# BLE_Board_WB55.net
KiCad netlist of a schematic drawn in EAGLE
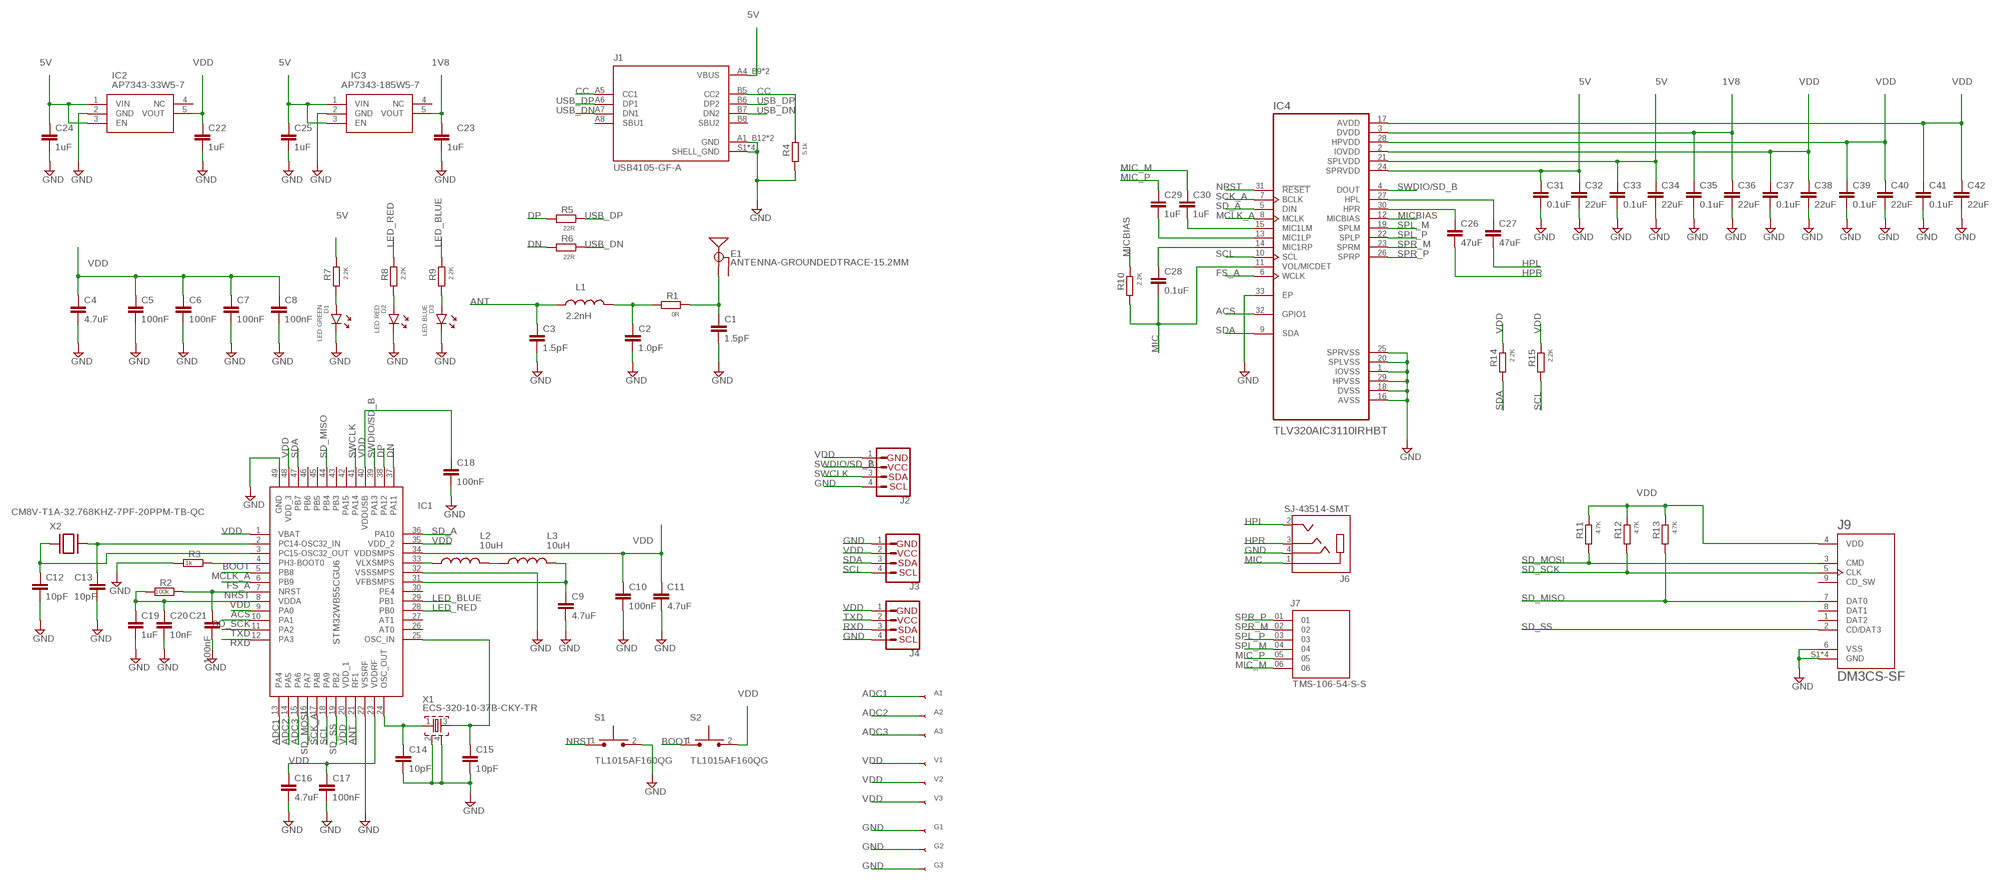
[diagram p0: schematic, sheet 1]

(export (version "E")
  (design (tool "Eeschema 10.0.6"))
  (components
    (comp (ref "A1")
      (value "ATP-50")
      (footprint "eagle-import:ATP-50")
      (libsource (lib "eagle-import") (part "ATP-50"))
    )
    (comp (ref "A2")
      (value "ATP-50")
      (footprint "eagle-import:ATP-50")
      (libsource (lib "eagle-import") (part "ATP-50"))
    )
    (comp (ref "A3")
      (value "ATP-50")
      (footprint "eagle-import:ATP-50")
      (libsource (lib "eagle-import") (part "ATP-50"))
    )
    (comp (ref "C1")
      (value "1.5pF")
      (footprint "eagle-import:RESC0402_N")
      (libsource (lib "eagle-import") (part "CAPACITOR_0402_N"))
    )
    (comp (ref "C2")
      (value "1.0pF")
      (footprint "eagle-import:RESC0402_N")
      (libsource (lib "eagle-import") (part "CAPACITOR_0402_N"))
    )
    (comp (ref "C3")
      (value "1.5pF")
      (footprint "eagle-import:RESC0402_N")
      (libsource (lib "eagle-import") (part "CAPACITOR_0402_N"))
    )
    (comp (ref "C4")
      (value "4.7uF")
      (footprint "eagle-import:RESC0603_N")
      (libsource (lib "eagle-import") (part "CAPACITOR_0603_N"))
    )
    (comp (ref "C5")
      (value "100nF")
      (footprint "eagle-import:RESC0603_N")
      (libsource (lib "eagle-import") (part "CAPACITOR_0603_N"))
    )
    (comp (ref "C6")
      (value "100nF")
      (footprint "eagle-import:RESC0603_N")
      (libsource (lib "eagle-import") (part "CAPACITOR_0603_N"))
    )
    (comp (ref "C7")
      (value "100nF")
      (footprint "eagle-import:RESC0603_N")
      (libsource (lib "eagle-import") (part "CAPACITOR_0603_N"))
    )
    (comp (ref "C8")
      (value "100nF")
      (footprint "eagle-import:RESC0603_N")
      (libsource (lib "eagle-import") (part "CAPACITOR_0603_N"))
    )
    (comp (ref "C9")
      (value "4.7uF")
      (footprint "eagle-import:RESC0603_N")
      (libsource (lib "eagle-import") (part "CAPACITOR_0603_N"))
    )
    (comp (ref "C10")
      (value "100nF")
      (footprint "eagle-import:RESC0603_N")
      (libsource (lib "eagle-import") (part "CAPACITOR_0603_N"))
    )
    (comp (ref "C11")
      (value "4.7uF")
      (footprint "eagle-import:RESC0603_N")
      (libsource (lib "eagle-import") (part "CAPACITOR_0603_N"))
    )
    (comp (ref "C12")
      (value "10pF")
      (footprint "eagle-import:RESC0402_N")
      (libsource (lib "eagle-import") (part "CAPACITOR_0402_N"))
    )
    (comp (ref "C13")
      (value "10pF")
      (footprint "eagle-import:RESC0402_N")
      (libsource (lib "eagle-import") (part "CAPACITOR_0402_N"))
    )
    (comp (ref "C14")
      (value "10pF")
      (footprint "eagle-import:RESC0402_N")
      (libsource (lib "eagle-import") (part "CAPACITOR_0402_N"))
    )
    (comp (ref "C15")
      (value "10pF")
      (footprint "eagle-import:RESC0402_N")
      (libsource (lib "eagle-import") (part "CAPACITOR_0402_N"))
    )
    (comp (ref "C16")
      (value "4.7uF")
      (footprint "eagle-import:RESC0603_N")
      (libsource (lib "eagle-import") (part "CAPACITOR_0603_N"))
    )
    (comp (ref "C17")
      (value "100nF")
      (footprint "eagle-import:RESC0603_N")
      (libsource (lib "eagle-import") (part "CAPACITOR_0603_N"))
    )
    (comp (ref "C18")
      (value "100nF")
      (footprint "eagle-import:RESC0603_N")
      (libsource (lib "eagle-import") (part "CAPACITOR_0603_N"))
    )
    (comp (ref "C19")
      (value "1uF")
      (footprint "eagle-import:RESC0603_N")
      (libsource (lib "eagle-import") (part "CAPACITOR_0603_N"))
    )
    (comp (ref "C20")
      (value "10nF")
      (footprint "eagle-import:RESC0603_N")
      (libsource (lib "eagle-import") (part "CAPACITOR_0603_N"))
    )
    (comp (ref "C21")
      (value "100nF")
      (footprint "eagle-import:RESC0603_N")
      (libsource (lib "eagle-import") (part "CAPACITOR_0603_N"))
    )
    (comp (ref "C22")
      (value "1uF")
      (footprint "eagle-import:RESC0603_N")
      (libsource (lib "eagle-import") (part "CAPACITOR_0603_N"))
    )
    (comp (ref "C23")
      (value "1uF")
      (footprint "eagle-import:RESC0603_N")
      (libsource (lib "eagle-import") (part "CAPACITOR_0603_N"))
    )
    (comp (ref "C24")
      (value "1uF")
      (footprint "eagle-import:RESC0603_N")
      (libsource (lib "eagle-import") (part "CAPACITOR_0603_N"))
    )
    (comp (ref "C25")
      (value "1uF")
      (footprint "eagle-import:RESC0603_N")
      (libsource (lib "eagle-import") (part "CAPACITOR_0603_N"))
    )
    (comp (ref "C26")
      (value "47uF")
      (footprint "eagle-import:RESC0603_N")
      (libsource (lib "eagle-import") (part "CAPACITOR_0603_N"))
    )
    (comp (ref "C27")
      (value "47uF")
      (footprint "eagle-import:RESC0603_N")
      (libsource (lib "eagle-import") (part "CAPACITOR_0603_N"))
    )
    (comp (ref "C28")
      (value "0.1uF")
      (footprint "eagle-import:RESC0603_N")
      (libsource (lib "eagle-import") (part "CAPACITOR_0603_N"))
    )
    (comp (ref "C29")
      (value "1uF")
      (footprint "eagle-import:RESC0603_N")
      (libsource (lib "eagle-import") (part "CAPACITOR_0603_N"))
    )
    (comp (ref "C30")
      (value "1uF")
      (footprint "eagle-import:RESC0603_N")
      (libsource (lib "eagle-import") (part "CAPACITOR_0603_N"))
    )
    (comp (ref "C31")
      (value "0.1uF")
      (footprint "eagle-import:RESC0603_N")
      (libsource (lib "eagle-import") (part "CAPACITOR_0603_N"))
    )
    (comp (ref "C32")
      (value "22uF")
      (footprint "eagle-import:RESC0603_N")
      (libsource (lib "eagle-import") (part "CAPACITOR_0603_N"))
    )
    (comp (ref "C33")
      (value "0.1uF")
      (footprint "eagle-import:RESC0603_N")
      (libsource (lib "eagle-import") (part "CAPACITOR_0603_N"))
    )
    (comp (ref "C34")
      (value "22uF")
      (footprint "eagle-import:RESC0603_N")
      (libsource (lib "eagle-import") (part "CAPACITOR_0603_N"))
    )
    (comp (ref "C35")
      (value "0.1uF")
      (footprint "eagle-import:RESC0603_N")
      (libsource (lib "eagle-import") (part "CAPACITOR_0603_N"))
    )
    (comp (ref "C36")
      (value "22uF")
      (footprint "eagle-import:RESC0603_N")
      (libsource (lib "eagle-import") (part "CAPACITOR_0603_N"))
    )
    (comp (ref "C37")
      (value "0.1uF")
      (footprint "eagle-import:RESC0603_N")
      (libsource (lib "eagle-import") (part "CAPACITOR_0603_N"))
    )
    (comp (ref "C38")
      (value "22uF")
      (footprint "eagle-import:RESC0603_N")
      (libsource (lib "eagle-import") (part "CAPACITOR_0603_N"))
    )
    (comp (ref "C39")
      (value "0.1uF")
      (footprint "eagle-import:RESC0603_N")
      (libsource (lib "eagle-import") (part "CAPACITOR_0603_N"))
    )
    (comp (ref "C40")
      (value "22uF")
      (footprint "eagle-import:RESC0603_N")
      (libsource (lib "eagle-import") (part "CAPACITOR_0603_N"))
    )
    (comp (ref "C41")
      (value "0.1uF")
      (footprint "eagle-import:RESC0603_N")
      (libsource (lib "eagle-import") (part "CAPACITOR_0603_N"))
    )
    (comp (ref "C42")
      (value "22uF")
      (footprint "eagle-import:RESC0603_N")
      (libsource (lib "eagle-import") (part "CAPACITOR_0603_N"))
    )
    (comp (ref "D1")
      (value "LED GREEN")
      (footprint "eagle-import:DIOC0603_N")
      (libsource (lib "eagle-import") (part "LED"))
    )
    (comp (ref "D2")
      (value "LED RED")
      (footprint "eagle-import:DIOC0603_N")
      (libsource (lib "eagle-import") (part "LED"))
    )
    (comp (ref "D3")
      (value "LED BLUE")
      (footprint "eagle-import:DIOC0603_N")
      (libsource (lib "eagle-import") (part "LED"))
    )
    (comp (ref "E1")
      (value "ANTENNA-GROUNDEDTRACE-15.2MM")
      (footprint "eagle-import:TRACE_ANTENNA_2.4GHZ_15.2MM")
      (libsource (lib "eagle-import") (part "ANTENNA-GROUNDEDTRACE-15.2MM"))
    )
    (comp (ref "G1")
      (value "ATP-50")
      (footprint "eagle-import:ATP-50")
      (libsource (lib "eagle-import") (part "ATP-50"))
    )
    (comp (ref "G2")
      (value "ATP-50")
      (footprint "eagle-import:ATP-50")
      (libsource (lib "eagle-import") (part "ATP-50"))
    )
    (comp (ref "G3")
      (value "ATP-50")
      (footprint "eagle-import:ATP-50")
      (libsource (lib "eagle-import") (part "ATP-50"))
    )
    (comp (ref "IC1")
      (value "STM32WB55CGU6")
      (footprint "eagle-import:QFN50P700X700X60-49N")
      (fields (field (name "MOUSER_PART_NUMBER") "511-STM32WB55CGU6"))
      (libsource (lib "eagle-import") (part "STM32WB55CGU6"))
    )
    (comp (ref "IC2")
      (value "AP7343-33W5-7")
      (footprint "eagle-import:SOT95P285X140-5N")
      (fields (field (name "MOUSER_PART_NUMBER") "621-AP7343-33W5-7"))
      (libsource (lib "eagle-import") (part "AP7343-33W5-7"))
    )
    (comp (ref "IC3")
      (value "AP7343-185W5-7")
      (footprint "eagle-import:SOT95P285X140-5N")
      (fields (field (name "MOUSER_PART_NUMBER") "621-AP7343-185W5-7"))
      (libsource (lib "eagle-import") (part "AP7343-185W5-7"))
    )
    (comp (ref "IC4")
      (value "TLV320AIC3110IRHBT")
      (footprint "eagle-import:IC_ADS125H01IRHBT")
      (fields (field (name "MF") "Texas Instruments"))
      (libsource (lib "eagle-import") (part "TLV320AIC3110IRHBT"))
    )
    (comp (ref "J1")
      (value "USB4105-GF-A")
      (footprint "eagle-import:GCT_USB4105-GF-A")
      (fields (field (name "MF") "GCT"))
      (libsource (lib "eagle-import") (part "USB4105-GF-A"))
    )
    (comp (ref "J2")
      (value "QWIIC_CONNECTORJS-1MM")
      (footprint "eagle-import:1X04_1MM_RA")
      (libsource (lib "eagle-import") (part "QWIIC_CONNECTORJS-1MM"))
    )
    (comp (ref "J3")
      (value "QWIIC_CONNECTORJS-1MM")
      (footprint "eagle-import:1X04_1MM_RA")
      (libsource (lib "eagle-import") (part "QWIIC_CONNECTORJS-1MM"))
    )
    (comp (ref "J4")
      (value "QWIIC_CONNECTORJS-1MM")
      (footprint "eagle-import:1X04_1MM_RA")
      (libsource (lib "eagle-import") (part "QWIIC_CONNECTORJS-1MM"))
    )
    (comp (ref "J6")
      (value "SJ-43514-SMT")
      (footprint "eagle-import:CUI_SJ-43514-SMT")
      (fields (field (name "MF") "CUI Devices") (field (name "MP") "SJ-43514-SMT-TR"))
      (libsource (lib "eagle-import") (part "SJ-43514-SMT"))
    )
    (comp (ref "J7")
      (value "TMS-106-54-S-S")
      (footprint "eagle-import:SAMTEC_TMS-106-54-S-S")
      (fields (field (name "MF") "Samtec"))
      (libsource (lib "eagle-import") (part "TMS-106-54-S-S"))
    )
    (comp (ref "J9")
      (value "DM3CS-SF")
      (footprint "eagle-import:HRS_DM3CS-SF")
      (fields (field (name "MF") "Hirose"))
      (libsource (lib "eagle-import") (part "DM3CS-SF"))
    )
    (comp (ref "L1")
      (value "2.2nH")
      (footprint "eagle-import:RESC0402_N")
      (libsource (lib "eagle-import") (part "INDUCTOR_0402_N"))
    )
    (comp (ref "L2")
      (value "10uH")
      (footprint "eagle-import:RESC0603_N")
      (libsource (lib "eagle-import") (part "INDUCTOR_0603_N"))
    )
    (comp (ref "L3")
      (value "10uH")
      (footprint "eagle-import:RESC0603_N")
      (libsource (lib "eagle-import") (part "INDUCTOR_0603_N"))
    )
    (comp (ref "R1")
      (value "0R")
      (footprint "eagle-import:RESC0402_N")
      (libsource (lib "eagle-import") (part "RESISTOR_0402_N"))
    )
    (comp (ref "R2")
      (value "100k")
      (footprint "eagle-import:RESC0603_N")
      (libsource (lib "eagle-import") (part "RESISTOR_0603_N"))
    )
    (comp (ref "R3")
      (value "1k")
      (footprint "eagle-import:RESC0603_N")
      (libsource (lib "eagle-import") (part "RESISTOR_0603_N"))
    )
    (comp (ref "R4")
      (value "5.1k")
      (footprint "eagle-import:RESC0603_N")
      (libsource (lib "eagle-import") (part "RESISTOR_0603_N"))
    )
    (comp (ref "R5")
      (value "22R")
      (footprint "eagle-import:RESC0603_N")
      (libsource (lib "eagle-import") (part "RESISTOR_0603_N"))
    )
    (comp (ref "R6")
      (value "22R")
      (footprint "eagle-import:RESC0603_N")
      (libsource (lib "eagle-import") (part "RESISTOR_0603_N"))
    )
    (comp (ref "R7")
      (value "2.2K")
      (footprint "eagle-import:RESC0603_N")
      (libsource (lib "eagle-import") (part "RESISTOR_0603_N"))
    )
    (comp (ref "R8")
      (value "2.2K")
      (footprint "eagle-import:RESC0603_N")
      (libsource (lib "eagle-import") (part "RESISTOR_0603_N"))
    )
    (comp (ref "R9")
      (value "2.2K")
      (footprint "eagle-import:RESC0603_N")
      (libsource (lib "eagle-import") (part "RESISTOR_0603_N"))
    )
    (comp (ref "R10")
      (value "2.2K")
      (footprint "eagle-import:RESC0603_N")
      (libsource (lib "eagle-import") (part "RESISTOR_0603_N"))
    )
    (comp (ref "R11")
      (value "4.7K")
      (footprint "eagle-import:RESC0603_N")
      (libsource (lib "eagle-import") (part "RESISTOR_0603_N"))
    )
    (comp (ref "R12")
      (value "4.7K")
      (footprint "eagle-import:RESC0603_N")
      (libsource (lib "eagle-import") (part "RESISTOR_0603_N"))
    )
    (comp (ref "R13")
      (value "4.7K")
      (footprint "eagle-import:RESC0603_N")
      (libsource (lib "eagle-import") (part "RESISTOR_0603_N"))
    )
    (comp (ref "R14")
      (value "2.2K")
      (footprint "eagle-import:RESC0603_N")
      (libsource (lib "eagle-import") (part "RESISTOR_0603_N"))
    )
    (comp (ref "R15")
      (value "2.2K")
      (footprint "eagle-import:RESC0603_N")
      (libsource (lib "eagle-import") (part "RESISTOR_0603_N"))
    )
    (comp (ref "S1")
      (value "TL1015AF160QG")
      (footprint "eagle-import:SW_TL1015AF160QG")
      (fields (field (name "MF") "E-Switch"))
      (libsource (lib "eagle-import") (part "TL1015AF160QG"))
    )
    (comp (ref "S2")
      (value "TL1015AF160QG")
      (footprint "eagle-import:SW_TL1015AF160QG")
      (fields (field (name "MF") "E-Switch"))
      (libsource (lib "eagle-import") (part "TL1015AF160QG"))
    )
    (comp (ref "V1")
      (value "ATP-50")
      (footprint "eagle-import:ATP-50")
      (libsource (lib "eagle-import") (part "ATP-50"))
    )
    (comp (ref "V2")
      (value "ATP-50")
      (footprint "eagle-import:ATP-50")
      (libsource (lib "eagle-import") (part "ATP-50"))
    )
    (comp (ref "V3")
      (value "ATP-50")
      (footprint "eagle-import:ATP-50")
      (libsource (lib "eagle-import") (part "ATP-50"))
    )
    (comp (ref "X1")
      (value "ECS-320-10-37B-CKY-TR")
      (footprint "eagle-import:BT-XTAL_2016_N")
      (libsource (lib "eagle-import") (part "XTAL_32MHZ"))
    )
    (comp (ref "X2")
      (value "CM8V-T1A-32.768KHZ-7PF-20PPM-TB-QC")
      (footprint "eagle-import:XTAL_CM8V-T1A-32.768KHZ-7PF-20PPM-TB-QC")
      (fields (field (name "MF") "Micro Crystal AG"))
      (libsource (lib "eagle-import") (part "CM8V-T1A-32.768KHZ-7PF-20PPM-TB-QC"))
    )
  )
  (nets
    (net (code "1") (name "/1V8") (class "Default")
      (node (ref "C23") (pin "1") (pinfunction "1_1") (pintype "passive"))
      (node (ref "C35") (pin "1") (pinfunction "1_1") (pintype "passive"))
      (node (ref "C36") (pin "1") (pinfunction "1_1") (pintype "passive"))
      (node (ref "IC3") (pin "5") (pinfunction "VOUT_5") (pintype "bidirectional"))
      (node (ref "IC4") (pin "3") (pinfunction "DVDD_3") (pintype "power_in"))
    )
    (net (code "2") (name "/5V") (class "Default")
      (node (ref "C24") (pin "1") (pinfunction "1_1") (pintype "passive"))
      (node (ref "C25") (pin "1") (pinfunction "1_1") (pintype "passive"))
      (node (ref "C31") (pin "1") (pinfunction "1_1") (pintype "passive"))
      (node (ref "C32") (pin "1") (pinfunction "1_1") (pintype "passive"))
      (node (ref "C33") (pin "1") (pinfunction "1_1") (pintype "passive"))
      (node (ref "C34") (pin "1") (pinfunction "1_1") (pintype "passive"))
      (node (ref "IC2") (pin "1") (pinfunction "VIN_1") (pintype "bidirectional"))
      (node (ref "IC2") (pin "3") (pinfunction "EN_3") (pintype "bidirectional"))
      (node (ref "IC3") (pin "1") (pinfunction "VIN_1") (pintype "bidirectional"))
      (node (ref "IC3") (pin "3") (pinfunction "EN_3") (pintype "bidirectional"))
      (node (ref "IC4") (pin "21") (pinfunction "SPLVDD_21") (pintype "power_in"))
      (node (ref "IC4") (pin "24") (pinfunction "SPRVDD_24") (pintype "power_in"))
      (node (ref "J1") (pin "A4_B9") (pinfunction "VBUS_A4_B9") (pintype "power_in"))
      (node (ref "J1") (pin "B4_A9") (pinfunction "VBUS_B4_A9") (pintype "power_in"))
      (node (ref "R7") (pin "1") (pinfunction "1_1") (pintype "passive"))
    )
    (net (code "3") (name "/ACS") (class "Default")
      (node (ref "IC1") (pin "9") (pinfunction "PA0_9") (pintype "bidirectional"))
      (node (ref "IC4") (pin "32") (pinfunction "GPIO1_32") (pintype "bidirectional"))
    )
    (net (code "4") (name "/ADC1") (class "Default")
      (node (ref "A1") (pin "P") (pinfunction "TP_P") (pintype "passive"))
      (node (ref "IC1") (pin "13") (pinfunction "PA4_13") (pintype "bidirectional"))
    )
    (net (code "5") (name "/ADC2") (class "Default")
      (node (ref "A2") (pin "P") (pinfunction "TP_P") (pintype "passive"))
      (node (ref "IC1") (pin "14") (pinfunction "PA5_14") (pintype "bidirectional"))
    )
    (net (code "6") (name "/ADC3") (class "Default")
      (node (ref "A3") (pin "P") (pinfunction "TP_P") (pintype "passive"))
      (node (ref "IC1") (pin "15") (pinfunction "PA6_15") (pintype "bidirectional"))
    )
    (net (code "7") (name "/ANT") (class "Default")
      (node (ref "C3") (pin "1") (pinfunction "1_1") (pintype "passive"))
      (node (ref "IC1") (pin "21") (pinfunction "RF1_21") (pintype "bidirectional"))
      (node (ref "L1") (pin "1") (pinfunction "1_1") (pintype "passive"))
    )
    (net (code "8") (name "/BOOT") (class "Default")
      (node (ref "IC1") (pin "4") (pinfunction "PH3-BOOT0_4") (pintype "bidirectional"))
      (node (ref "R3") (pin "1") (pinfunction "1_1") (pintype "passive"))
      (node (ref "S2") (pin "1") (pinfunction "1_1") (pintype "passive"))
    )
    (net (code "9") (name "/CC") (class "Default")
      (node (ref "J1") (pin "A5") (pinfunction "CC1_A5") (pintype "bidirectional"))
      (node (ref "J1") (pin "B5") (pinfunction "CC2_B5") (pintype "bidirectional"))
      (node (ref "R4") (pin "1") (pinfunction "1_1") (pintype "passive"))
    )
    (net (code "10") (name "/DN") (class "Default")
      (node (ref "IC1") (pin "37") (pinfunction "PA11_37") (pintype "bidirectional"))
      (node (ref "R6") (pin "2") (pinfunction "2_2") (pintype "passive"))
    )
    (net (code "11") (name "/DP") (class "Default")
      (node (ref "IC1") (pin "38") (pinfunction "PA12_38") (pintype "bidirectional"))
      (node (ref "R5") (pin "2") (pinfunction "2_2") (pintype "passive"))
    )
    (net (code "12") (name "/FS_A") (class "Default")
      (node (ref "IC1") (pin "6") (pinfunction "PB9_6") (pintype "bidirectional"))
      (node (ref "IC4") (pin "6") (pinfunction "WCLK_6") (pintype "input"))
    )
    (net (code "13") (name "/HPL") (class "Default")
      (node (ref "C27") (pin "2") (pinfunction "2_2") (pintype "passive"))
      (node (ref "J6") (pin "2") (pinfunction "TIP_2") (pintype "passive"))
    )
    (net (code "14") (name "/HPR") (class "Default")
      (node (ref "C26") (pin "2") (pinfunction "2_2") (pintype "passive"))
      (node (ref "J6") (pin "3") (pinfunction "RING1_3") (pintype "passive"))
    )
    (net (code "15") (name "/LED_BLUE") (class "Default")
      (node (ref "IC1") (pin "29") (pinfunction "PB1_29") (pintype "bidirectional"))
      (node (ref "R9") (pin "1") (pinfunction "1_1") (pintype "passive"))
    )
    (net (code "16") (name "/LED_RED") (class "Default")
      (node (ref "IC1") (pin "28") (pinfunction "PB0_28") (pintype "bidirectional"))
      (node (ref "R8") (pin "1") (pinfunction "1_1") (pintype "passive"))
    )
    (net (code "17") (name "/MCLK_A") (class "Default")
      (node (ref "IC1") (pin "5") (pinfunction "PB8_5") (pintype "bidirectional"))
      (node (ref "IC4") (pin "8") (pinfunction "MCLK_8") (pintype "input"))
    )
    (net (code "18") (name "/MIC") (class "Default")
      (node (ref "C28") (pin "2") (pinfunction "2_2") (pintype "passive"))
      (node (ref "IC4") (pin "11") (pinfunction "VOL/MICDET_11") (pintype "input"))
      (node (ref "J6") (pin "1") (pinfunction "SLEEVE_1") (pintype "passive"))
      (node (ref "R10") (pin "2") (pinfunction "2_2") (pintype "passive"))
    )
    (net (code "19") (name "/MICBIAS") (class "Default")
      (node (ref "IC4") (pin "12") (pinfunction "MICBIAS_12") (pintype "output"))
      (node (ref "R10") (pin "1") (pinfunction "1_1") (pintype "passive"))
    )
    (net (code "20") (name "/MIC_M") (class "Default")
      (node (ref "C30") (pin "1") (pinfunction "1_1") (pintype "passive"))
      (node (ref "J7") (pin "06") (pinfunction "06_06") (pintype "passive"))
    )
    (net (code "21") (name "/MIC_P") (class "Default")
      (node (ref "C29") (pin "1") (pinfunction "1_1") (pintype "passive"))
      (node (ref "J7") (pin "05") (pinfunction "05_05") (pintype "passive"))
    )
    (net (code "22") (name "/NRST") (class "Default")
      (node (ref "C21") (pin "1") (pinfunction "1_1") (pintype "passive"))
      (node (ref "IC1") (pin "7") (pinfunction "NRST_7") (pintype "bidirectional"))
      (node (ref "IC4") (pin "31") (pinfunction "~{RESET}_31") (pintype "input"))
      (node (ref "R2") (pin "1") (pinfunction "1_1") (pintype "passive"))
      (node (ref "S1") (pin "1") (pinfunction "1_1") (pintype "passive"))
    )
    (net (code "23") (name "/RXD") (class "Default")
      (node (ref "IC1") (pin "12") (pinfunction "PA3_12") (pintype "bidirectional"))
      (node (ref "J4") (pin "3") (pinfunction "3_3") (pintype "passive"))
    )
    (net (code "24") (name "/SCK_A") (class "Default")
      (node (ref "IC1") (pin "17") (pinfunction "PA8_17") (pintype "bidirectional"))
      (node (ref "IC4") (pin "7") (pinfunction "BCLK_7") (pintype "input"))
    )
    (net (code "25") (name "/SCL") (class "Default")
      (node (ref "IC1") (pin "18") (pinfunction "PA9_18") (pintype "bidirectional"))
      (node (ref "IC4") (pin "10") (pinfunction "SCL_10") (pintype "input"))
      (node (ref "J3") (pin "4") (pinfunction "4_4") (pintype "passive"))
      (node (ref "R15") (pin "2") (pinfunction "2_2") (pintype "passive"))
    )
    (net (code "26") (name "/SDA") (class "Default")
      (node (ref "IC1") (pin "47") (pinfunction "PB7_47") (pintype "bidirectional"))
      (node (ref "IC4") (pin "9") (pinfunction "SDA_9") (pintype "bidirectional"))
      (node (ref "J3") (pin "3") (pinfunction "3_3") (pintype "passive"))
      (node (ref "R14") (pin "2") (pinfunction "2_2") (pintype "passive"))
    )
    (net (code "27") (name "/SD_A") (class "Default")
      (node (ref "IC1") (pin "36") (pinfunction "PA10_36") (pintype "bidirectional"))
      (node (ref "IC4") (pin "5") (pinfunction "DIN_5") (pintype "input"))
    )
    (net (code "28") (name "/SD_MISO") (class "Default")
      (node (ref "IC1") (pin "44") (pinfunction "PB4_44") (pintype "bidirectional"))
      (node (ref "J9") (pin "7") (pinfunction "DAT0_7") (pintype "passive"))
      (node (ref "R13") (pin "2") (pinfunction "2_2") (pintype "passive"))
    )
    (net (code "29") (name "/SD_MOSI") (class "Default")
      (node (ref "IC1") (pin "16") (pinfunction "PA7_16") (pintype "bidirectional"))
      (node (ref "J9") (pin "3") (pinfunction "CMD_3") (pintype "passive"))
      (node (ref "R11") (pin "2") (pinfunction "2_2") (pintype "passive"))
    )
    (net (code "30") (name "/SD_SCK") (class "Default")
      (node (ref "IC1") (pin "10") (pinfunction "PA1_10") (pintype "bidirectional"))
      (node (ref "J9") (pin "5") (pinfunction "CLK_5") (pintype "passive"))
      (node (ref "R12") (pin "2") (pinfunction "2_2") (pintype "passive"))
    )
    (net (code "31") (name "/SD_SS") (class "Default")
      (node (ref "IC1") (pin "19") (pinfunction "PB2_19") (pintype "bidirectional"))
      (node (ref "J9") (pin "2") (pinfunction "CD/DAT3_2") (pintype "passive"))
    )
    (net (code "32") (name "/SPL_M") (class "Default")
      (node (ref "IC4") (pin "19") (pinfunction "SPLM_19") (pintype "output"))
      (node (ref "J7") (pin "04") (pinfunction "04_04") (pintype "passive"))
    )
    (net (code "33") (name "/SPL_P") (class "Default")
      (node (ref "IC4") (pin "22") (pinfunction "SPLP_22") (pintype "output"))
      (node (ref "J7") (pin "03") (pinfunction "03_03") (pintype "passive"))
    )
    (net (code "34") (name "/SPR_M") (class "Default")
      (node (ref "IC4") (pin "23") (pinfunction "SPRM_23") (pintype "output"))
      (node (ref "J7") (pin "02") (pinfunction "02_02") (pintype "passive"))
    )
    (net (code "35") (name "/SPR_P") (class "Default")
      (node (ref "IC4") (pin "26") (pinfunction "SPRP_26") (pintype "output"))
      (node (ref "J7") (pin "01") (pinfunction "01_01") (pintype "passive"))
    )
    (net (code "36") (name "/SWCLK") (class "Default")
      (node (ref "IC1") (pin "41") (pinfunction "PA14_41") (pintype "bidirectional"))
      (node (ref "J2") (pin "3") (pinfunction "3_3") (pintype "passive"))
    )
    (net (code "37") (name "/SWDIO{slash}SD_B") (class "Default")
      (node (ref "IC1") (pin "39") (pinfunction "PA13_39") (pintype "bidirectional"))
      (node (ref "IC4") (pin "4") (pinfunction "DOUT_4") (pintype "output"))
      (node (ref "J2") (pin "2") (pinfunction "2_2") (pintype "power_in"))
    )
    (net (code "38") (name "/TXD") (class "Default")
      (node (ref "IC1") (pin "11") (pinfunction "PA2_11") (pintype "bidirectional"))
      (node (ref "J4") (pin "2") (pinfunction "2_2") (pintype "power_in"))
    )
    (net (code "39") (name "/USB_DN") (class "Default")
      (node (ref "J1") (pin "A7") (pinfunction "DN1_A7") (pintype "bidirectional"))
      (node (ref "J1") (pin "B7") (pinfunction "DN2_B7") (pintype "bidirectional"))
      (node (ref "R6") (pin "1") (pinfunction "1_1") (pintype "passive"))
    )
    (net (code "40") (name "/USB_DP") (class "Default")
      (node (ref "J1") (pin "A6") (pinfunction "DP1_A6") (pintype "bidirectional"))
      (node (ref "J1") (pin "B6") (pinfunction "DP2_B6") (pintype "bidirectional"))
      (node (ref "R5") (pin "1") (pinfunction "1_1") (pintype "passive"))
    )
    (net (code "41") (name "/VDD") (class "Default")
      (node (ref "C10") (pin "1") (pinfunction "1_1") (pintype "passive"))
      (node (ref "C11") (pin "1") (pinfunction "1_1") (pintype "passive"))
      (node (ref "C16") (pin "1") (pinfunction "1_1") (pintype "passive"))
      (node (ref "C17") (pin "1") (pinfunction "1_1") (pintype "passive"))
      (node (ref "C18") (pin "1") (pinfunction "1_1") (pintype "passive"))
      (node (ref "C19") (pin "1") (pinfunction "1_1") (pintype "passive"))
      (node (ref "C20") (pin "1") (pinfunction "1_1") (pintype "passive"))
      (node (ref "C22") (pin "1") (pinfunction "1_1") (pintype "passive"))
      (node (ref "C37") (pin "1") (pinfunction "1_1") (pintype "passive"))
      (node (ref "C38") (pin "1") (pinfunction "1_1") (pintype "passive"))
      (node (ref "C39") (pin "1") (pinfunction "1_1") (pintype "passive"))
      (node (ref "C4") (pin "1") (pinfunction "1_1") (pintype "passive"))
      (node (ref "C40") (pin "1") (pinfunction "1_1") (pintype "passive"))
      (node (ref "C41") (pin "1") (pinfunction "1_1") (pintype "passive"))
      (node (ref "C42") (pin "1") (pinfunction "1_1") (pintype "passive"))
      (node (ref "C5") (pin "1") (pinfunction "1_1") (pintype "passive"))
      (node (ref "C6") (pin "1") (pinfunction "1_1") (pintype "passive"))
      (node (ref "C7") (pin "1") (pinfunction "1_1") (pintype "passive"))
      (node (ref "C8") (pin "1") (pinfunction "1_1") (pintype "passive"))
      (node (ref "IC1") (pin "1") (pinfunction "VBAT_1") (pintype "bidirectional"))
      (node (ref "IC1") (pin "20") (pinfunction "VDD_1_20") (pintype "bidirectional"))
      (node (ref "IC1") (pin "23") (pinfunction "VDDRF_23") (pintype "bidirectional"))
      (node (ref "IC1") (pin "34") (pinfunction "VDDSMPS_34") (pintype "bidirectional"))
      (node (ref "IC1") (pin "35") (pinfunction "VDD_2_35") (pintype "bidirectional"))
      (node (ref "IC1") (pin "40") (pinfunction "VDDUSB_40") (pintype "bidirectional"))
      (node (ref "IC1") (pin "48") (pinfunction "VDD_3_48") (pintype "bidirectional"))
      (node (ref "IC1") (pin "8") (pinfunction "VDDA_8") (pintype "bidirectional"))
      (node (ref "IC2") (pin "5") (pinfunction "VOUT_5") (pintype "bidirectional"))
      (node (ref "IC4") (pin "17") (pinfunction "AVDD_17") (pintype "power_in"))
      (node (ref "IC4") (pin "2") (pinfunction "IOVDD_2") (pintype "power_in"))
      (node (ref "IC4") (pin "28") (pinfunction "HPVDD_28") (pintype "power_in"))
      (node (ref "J2") (pin "1") (pinfunction "1_1") (pintype "power_in"))
      (node (ref "J3") (pin "2") (pinfunction "2_2") (pintype "power_in"))
      (node (ref "J4") (pin "1") (pinfunction "1_1") (pintype "power_in"))
      (node (ref "J9") (pin "4") (pinfunction "VDD_4") (pintype "passive"))
      (node (ref "R11") (pin "1") (pinfunction "1_1") (pintype "passive"))
      (node (ref "R12") (pin "1") (pinfunction "1_1") (pintype "passive"))
      (node (ref "R13") (pin "1") (pinfunction "1_1") (pintype "passive"))
      (node (ref "R14") (pin "1") (pinfunction "1_1") (pintype "passive"))
      (node (ref "R15") (pin "1") (pinfunction "1_1") (pintype "passive"))
      (node (ref "R2") (pin "2") (pinfunction "2_2") (pintype "passive"))
      (node (ref "S2") (pin "2") (pinfunction "2_2") (pintype "passive"))
      (node (ref "V1") (pin "P") (pinfunction "TP_P") (pintype "passive"))
      (node (ref "V2") (pin "P") (pinfunction "TP_P") (pintype "passive"))
      (node (ref "V3") (pin "P") (pinfunction "TP_P") (pintype "passive"))
    )
    (net (code "42") (name "GND") (class "Default")
      (node (ref "C1") (pin "2") (pinfunction "2_2") (pintype "passive"))
      (node (ref "C10") (pin "2") (pinfunction "2_2") (pintype "passive"))
      (node (ref "C11") (pin "2") (pinfunction "2_2") (pintype "passive"))
      (node (ref "C12") (pin "2") (pinfunction "2_2") (pintype "passive"))
      (node (ref "C13") (pin "2") (pinfunction "2_2") (pintype "passive"))
      (node (ref "C14") (pin "2") (pinfunction "2_2") (pintype "passive"))
      (node (ref "C15") (pin "2") (pinfunction "2_2") (pintype "passive"))
      (node (ref "C16") (pin "2") (pinfunction "2_2") (pintype "passive"))
      (node (ref "C17") (pin "2") (pinfunction "2_2") (pintype "passive"))
      (node (ref "C18") (pin "2") (pinfunction "2_2") (pintype "passive"))
      (node (ref "C19") (pin "2") (pinfunction "2_2") (pintype "passive"))
      (node (ref "C2") (pin "2") (pinfunction "2_2") (pintype "passive"))
      (node (ref "C20") (pin "2") (pinfunction "2_2") (pintype "passive"))
      (node (ref "C21") (pin "2") (pinfunction "2_2") (pintype "passive"))
      (node (ref "C22") (pin "2") (pinfunction "2_2") (pintype "passive"))
      (node (ref "C23") (pin "2") (pinfunction "2_2") (pintype "passive"))
      (node (ref "C24") (pin "2") (pinfunction "2_2") (pintype "passive"))
      (node (ref "C25") (pin "2") (pinfunction "2_2") (pintype "passive"))
      (node (ref "C3") (pin "2") (pinfunction "2_2") (pintype "passive"))
      (node (ref "C31") (pin "2") (pinfunction "2_2") (pintype "passive"))
      (node (ref "C32") (pin "2") (pinfunction "2_2") (pintype "passive"))
      (node (ref "C33") (pin "2") (pinfunction "2_2") (pintype "passive"))
      (node (ref "C34") (pin "2") (pinfunction "2_2") (pintype "passive"))
      (node (ref "C35") (pin "2") (pinfunction "2_2") (pintype "passive"))
      (node (ref "C36") (pin "2") (pinfunction "2_2") (pintype "passive"))
      (node (ref "C37") (pin "2") (pinfunction "2_2") (pintype "passive"))
      (node (ref "C38") (pin "2") (pinfunction "2_2") (pintype "passive"))
      (node (ref "C39") (pin "2") (pinfunction "2_2") (pintype "passive"))
      (node (ref "C4") (pin "2") (pinfunction "2_2") (pintype "passive"))
      (node (ref "C40") (pin "2") (pinfunction "2_2") (pintype "passive"))
      (node (ref "C41") (pin "2") (pinfunction "2_2") (pintype "passive"))
      (node (ref "C42") (pin "2") (pinfunction "2_2") (pintype "passive"))
      (node (ref "C5") (pin "2") (pinfunction "2_2") (pintype "passive"))
      (node (ref "C6") (pin "2") (pinfunction "2_2") (pintype "passive"))
      (node (ref "C7") (pin "2") (pinfunction "2_2") (pintype "passive"))
      (node (ref "C8") (pin "2") (pinfunction "2_2") (pintype "passive"))
      (node (ref "C9") (pin "2") (pinfunction "2_2") (pintype "passive"))
      (node (ref "D1") (pin "1") (pinfunction "C_1") (pintype "bidirectional"))
      (node (ref "D2") (pin "1") (pinfunction "C_1") (pintype "bidirectional"))
      (node (ref "D3") (pin "1") (pinfunction "C_1") (pintype "bidirectional"))
      (node (ref "G1") (pin "P") (pinfunction "TP_P") (pintype "passive"))
      (node (ref "G2") (pin "P") (pinfunction "TP_P") (pintype "passive"))
      (node (ref "G3") (pin "P") (pinfunction "TP_P") (pintype "passive"))
      (node (ref "IC1") (pin "22") (pinfunction "VSSRF_22") (pintype "bidirectional"))
      (node (ref "IC1") (pin "32") (pinfunction "VSSSMPS_32") (pintype "bidirectional"))
      (node (ref "IC1") (pin "49") (pinfunction "GND_49") (pintype "bidirectional"))
      (node (ref "IC2") (pin "2") (pinfunction "GND_2") (pintype "bidirectional"))
      (node (ref "IC3") (pin "2") (pinfunction "GND_2") (pintype "bidirectional"))
      (node (ref "IC4") (pin "1") (pinfunction "IOVSS_1") (pintype "power_in"))
      (node (ref "IC4") (pin "16") (pinfunction "AVSS_16") (pintype "power_in"))
      (node (ref "IC4") (pin "18") (pinfunction "DVSS_18") (pintype "power_in"))
      (node (ref "IC4") (pin "20") (pinfunction "SPLVSS_20") (pintype "power_in"))
      (node (ref "IC4") (pin "25") (pinfunction "SPRVSS_25") (pintype "power_in"))
      (node (ref "IC4") (pin "29") (pinfunction "HPVSS_29") (pintype "power_in"))
      (node (ref "IC4") (pin "33") (pinfunction "EP_33") (pintype "bidirectional"))
      (node (ref "J1") (pin "A1_B12") (pinfunction "GND_A1_B12") (pintype "power_in"))
      (node (ref "J1") (pin "B1_A12") (pinfunction "GND_B1_A12") (pintype "power_in"))
      (node (ref "J1") (pin "S1") (pinfunction "SHELL_GND_S1") (pintype "power_in"))
      (node (ref "J1") (pin "S2") (pinfunction "SHELL_GND_S2") (pintype "power_in"))
      (node (ref "J1") (pin "S3") (pinfunction "SHELL_GND_S3") (pintype "power_in"))
      (node (ref "J1") (pin "S4") (pinfunction "SHELL_GND_S4") (pintype "power_in"))
      (node (ref "J2") (pin "4") (pinfunction "4_4") (pintype "passive"))
      (node (ref "J3") (pin "1") (pinfunction "1_1") (pintype "power_in"))
      (node (ref "J4") (pin "4") (pinfunction "4_4") (pintype "passive"))
      (node (ref "J6") (pin "4") (pinfunction "RING2_4") (pintype "passive"))
      (node (ref "J9") (pin "6") (pinfunction "VSS_6") (pintype "passive"))
      (node (ref "J9") (pin "S1") (pinfunction "GND_S1") (pintype "passive"))
      (node (ref "J9") (pin "S2") (pinfunction "GND_S2") (pintype "passive"))
      (node (ref "J9") (pin "S3") (pinfunction "GND_S3") (pintype "passive"))
      (node (ref "J9") (pin "S5") (pinfunction "GND_S5") (pintype "passive"))
      (node (ref "R3") (pin "2") (pinfunction "2_2") (pintype "passive"))
      (node (ref "R4") (pin "2") (pinfunction "2_2") (pintype "passive"))
      (node (ref "S1") (pin "2") (pinfunction "2_2") (pintype "passive"))
      (node (ref "X1") (pin "2") (pinfunction "2_2") (pintype "passive"))
      (node (ref "X1") (pin "4") (pinfunction "4_4") (pintype "passive"))
    )
    (net (code "43") (name "Net-(C2-Pad1)") (class "Default")
      (node (ref "C2") (pin "1") (pinfunction "1_1") (pintype "passive"))
      (node (ref "L1") (pin "2") (pinfunction "2_2") (pintype "passive"))
      (node (ref "R1") (pin "1") (pinfunction "1_1") (pintype "passive"))
    )
    (net (code "44") (name "Net-(D1-A)") (class "Default")
      (node (ref "D1") (pin "2") (pinfunction "A_2") (pintype "bidirectional"))
      (node (ref "R7") (pin "2") (pinfunction "2_2") (pintype "passive"))
    )
    (net (code "45") (name "Net-(D2-A)") (class "Default")
      (node (ref "D2") (pin "2") (pinfunction "A_2") (pintype "bidirectional"))
      (node (ref "R8") (pin "2") (pinfunction "2_2") (pintype "passive"))
    )
    (net (code "46") (name "Net-(D3-A)") (class "Default")
      (node (ref "D3") (pin "2") (pinfunction "A_2") (pintype "bidirectional"))
      (node (ref "R9") (pin "2") (pinfunction "2_2") (pintype "passive"))
    )
    (net (code "47") (name "Net-(E1-SIGNAL)") (class "Default")
      (node (ref "C1") (pin "1") (pinfunction "1_1") (pintype "passive"))
      (node (ref "E1") (pin "ANT") (pinfunction "SIGNAL_ANT") (pintype "bidirectional"))
      (node (ref "R1") (pin "2") (pinfunction "2_2") (pintype "passive"))
    )
    (net (code "48") (name "Net-(IC1-OSC_IN)") (class "Default")
      (node (ref "C15") (pin "1") (pinfunction "1_1") (pintype "passive"))
      (node (ref "IC1") (pin "25") (pinfunction "OSC_IN_25") (pintype "bidirectional"))
      (node (ref "X1") (pin "3") (pinfunction "3_3") (pintype "passive"))
    )
    (net (code "49") (name "Net-(IC1-OSC_OUT)") (class "Default")
      (node (ref "C14") (pin "1") (pinfunction "1_1") (pintype "passive"))
      (node (ref "IC1") (pin "24") (pinfunction "OSC_OUT_24") (pintype "bidirectional"))
      (node (ref "X1") (pin "1") (pinfunction "1_1") (pintype "passive"))
    )
    (net (code "50") (name "Net-(IC1-PC14-OSC32_IN)") (class "Default")
      (node (ref "C13") (pin "1") (pinfunction "1_1") (pintype "passive"))
      (node (ref "IC1") (pin "2") (pinfunction "PC14-OSC32_IN_2") (pintype "bidirectional"))
      (node (ref "X2") (pin "2") (pinfunction "2_2") (pintype "passive"))
    )
    (net (code "51") (name "Net-(IC1-PC15-OSC32_OUT)") (class "Default")
      (node (ref "C12") (pin "1") (pinfunction "1_1") (pintype "passive"))
      (node (ref "IC1") (pin "3") (pinfunction "PC15-OSC32_OUT_3") (pintype "bidirectional"))
      (node (ref "X2") (pin "1") (pinfunction "1_1") (pintype "passive"))
    )
    (net (code "52") (name "Net-(IC1-VFBSMPS)") (class "Default")
      (node (ref "C9") (pin "1") (pinfunction "1_1") (pintype "passive"))
      (node (ref "IC1") (pin "31") (pinfunction "VFBSMPS_31") (pintype "bidirectional"))
      (node (ref "L3") (pin "2") (pinfunction "2_2") (pintype "passive"))
    )
    (net (code "53") (name "Net-(IC1-VLXSMPS)") (class "Default")
      (node (ref "IC1") (pin "33") (pinfunction "VLXSMPS_33") (pintype "bidirectional"))
      (node (ref "L2") (pin "1") (pinfunction "1_1") (pintype "passive"))
    )
    (net (code "54") (name "Net-(IC4-HPL)") (class "Default")
      (node (ref "C27") (pin "1") (pinfunction "1_1") (pintype "passive"))
      (node (ref "IC4") (pin "27") (pinfunction "HPL_27") (pintype "output"))
    )
    (net (code "55") (name "Net-(IC4-HPR)") (class "Default")
      (node (ref "C26") (pin "1") (pinfunction "1_1") (pintype "passive"))
      (node (ref "IC4") (pin "30") (pinfunction "HPR_30") (pintype "output"))
    )
    (net (code "56") (name "Net-(IC4-MIC1LM)") (class "Default")
      (node (ref "C30") (pin "2") (pinfunction "2_2") (pintype "passive"))
      (node (ref "IC4") (pin "15") (pinfunction "MIC1LM_15") (pintype "input"))
    )
    (net (code "57") (name "Net-(IC4-MIC1LP)") (class "Default")
      (node (ref "C29") (pin "2") (pinfunction "2_2") (pintype "passive"))
      (node (ref "IC4") (pin "13") (pinfunction "MIC1LP_13") (pintype "input"))
    )
    (net (code "58") (name "Net-(IC4-MIC1RP)") (class "Default")
      (node (ref "C28") (pin "1") (pinfunction "1_1") (pintype "passive"))
      (node (ref "IC4") (pin "14") (pinfunction "MIC1RP_14") (pintype "input"))
    )
    (net (code "59") (name "Net-(L2-Pad2)") (class "Default")
      (node (ref "L2") (pin "2") (pinfunction "2_2") (pintype "passive"))
      (node (ref "L3") (pin "1") (pinfunction "1_1") (pintype "passive"))
    )
    (net (code "60") (name "unconnected-(E1-PadGND)") (class "Default")
      (node (ref "E1") (pin "GND") (pinfunction "GND_GND") (pintype "bidirectional"))
    )
    (net (code "61") (name "unconnected-(IC1-AT0-Pad26)") (class "Default")
      (node (ref "IC1") (pin "26") (pinfunction "AT0_26") (pintype "bidirectional"))
    )
    (net (code "62") (name "unconnected-(IC1-AT1-Pad27)") (class "Default")
      (node (ref "IC1") (pin "27") (pinfunction "AT1_27") (pintype "bidirectional"))
    )
    (net (code "63") (name "unconnected-(IC1-PA15-Pad42)") (class "Default")
      (node (ref "IC1") (pin "42") (pinfunction "PA15_42") (pintype "bidirectional"))
    )
    (net (code "64") (name "unconnected-(IC1-PB3-Pad43)") (class "Default")
      (node (ref "IC1") (pin "43") (pinfunction "PB3_43") (pintype "bidirectional"))
    )
    (net (code "65") (name "unconnected-(IC1-PB5-Pad45)") (class "Default")
      (node (ref "IC1") (pin "45") (pinfunction "PB5_45") (pintype "bidirectional"))
    )
    (net (code "66") (name "unconnected-(IC1-PB6-Pad46)") (class "Default")
      (node (ref "IC1") (pin "46") (pinfunction "PB6_46") (pintype "bidirectional"))
    )
    (net (code "67") (name "unconnected-(IC1-PE4-Pad30)") (class "Default")
      (node (ref "IC1") (pin "30") (pinfunction "PE4_30") (pintype "bidirectional"))
    )
    (net (code "68") (name "unconnected-(IC2-NC-Pad4)") (class "Default")
      (node (ref "IC2") (pin "4") (pinfunction "NC_4") (pintype "no_connect"))
    )
    (net (code "69") (name "unconnected-(IC3-NC-Pad4)") (class "Default")
      (node (ref "IC3") (pin "4") (pinfunction "NC_4") (pintype "no_connect"))
    )
    (net (code "70") (name "unconnected-(J1-SBU1-PadA8)") (class "Default")
      (node (ref "J1") (pin "A8") (pinfunction "SBU1_A8") (pintype "bidirectional"))
    )
    (net (code "71") (name "unconnected-(J1-SBU2-PadB8)") (class "Default")
      (node (ref "J1") (pin "B8") (pinfunction "SBU2_B8") (pintype "bidirectional"))
    )
    (net (code "72") (name "unconnected-(J9-CD_SW-Pad9)") (class "Default")
      (node (ref "J9") (pin "9") (pinfunction "CD_SW_9") (pintype "passive"))
    )
    (net (code "73") (name "unconnected-(J9-DAT1-Pad8)") (class "Default")
      (node (ref "J9") (pin "8") (pinfunction "DAT1_8") (pintype "passive"))
    )
    (net (code "74") (name "unconnected-(J9-DAT2-Pad1)") (class "Default")
      (node (ref "J9") (pin "1") (pinfunction "DAT2_1") (pintype "passive"))
    )
  )
)
